# Power_Generation_-_LDO.net
KiCad netlist of a schematic drawn in Altium Designer
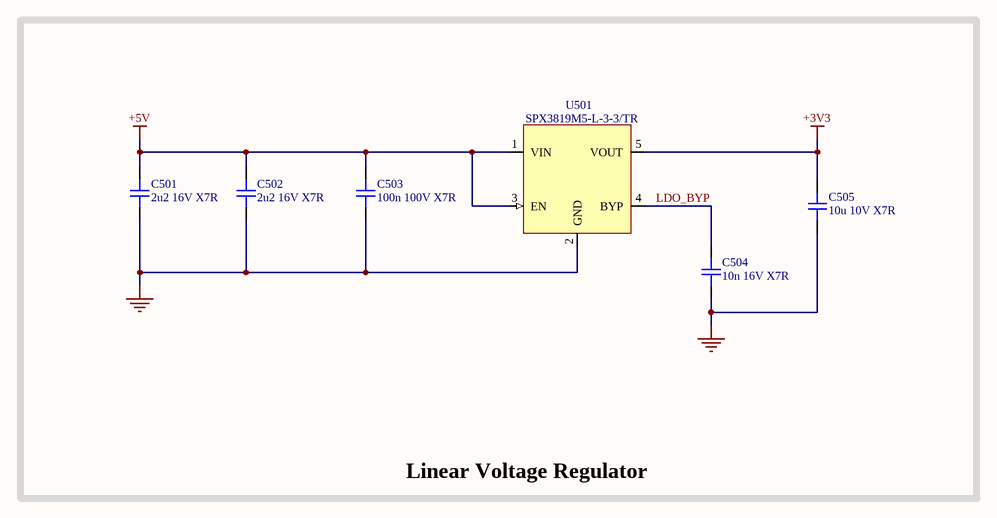
[diagram p0: Power Generation - LDO.SchDoc]

(export (version "E")
  (design (tool "Eeschema 10.0.6"))
  (components
    (comp (ref "C501")
      (value "2u2 16V X7R")
      (footprint "CAP_0805")
      (description "Capacitor SMD 0805")
      (fields
        (field (name "MANUFACTURER") "HRE")
        (field (name "MANUFACTURER PART NUMBER") "CGA0805X7R225K160MT")
      )
      (libsource (lib "Schematic-Lib-PhilsLab") (part "CAP_0805"))
    )
    (comp (ref "C502")
      (value "2u2 16V X7R")
      (footprint "CAP_0805")
      (description "Capacitor SMD 0805")
      (fields
        (field (name "MANUFACTURER") "HRE")
        (field (name "MANUFACTURER PART NUMBER") "CGA0805X7R225K160MT")
      )
      (libsource (lib "Schematic-Lib-PhilsLab") (part "CAP_0805"))
    )
    (comp (ref "C503")
      (value "100n 100V X7R")
      (footprint "CAP_0805")
      (description "Capacitor SMD 0805")
      (fields
        (field (name "MANUFACTURER") "YAGEO")
        (field (name "MANUFACTURER PART NUMBER") "CC0805JRX7R7BB104")
      )
      (libsource (lib "Schematic-Lib-PhilsLab") (part "CAP_0805"))
    )
    (comp (ref "C504")
      (value "10n 16V X7R")
      (footprint "CAP_0603")
      (description "Capacitor SMD 0603")
      (fields
        (field (name "MANUFACTURER") "YAGEO")
        (field (name "MANUFACTURER PART NUMBER") "CC0603JRX7R7BB103")
      )
      (libsource (lib "Schematic-Lib-PhilsLab") (part "CAP_0603"))
    )
    (comp (ref "C505")
      (value "10u 10V X7R")
      (footprint "CAP_0805")
      (description "Capacitor SMD 0805")
      (fields
        (field (name "MANUFACTURER") "Murata Electronics")
        (field (name "MANUFACTURER PART NUMBER") "GCM21BR71A106KE22K")
      )
      (libsource (lib "Schematic-Lib-PhilsLab") (part "CAP_0805"))
    )
    (comp (ref "U501")
      (value "SPX3819M5-L-3-3/TR")
      (footprint "SOT-23-5")
      (description "500mA +3.3V Low-Noise LDO Voltage Regulator")
      (fields (field (name "MANUFACTURER") "MaxLinear"))
      (libsource (lib "Schematic-Lib") (part "SPX3819M5-L-3-3/TR"))
    )
  )
  (nets
    (net (code "1") (name "+3V3") (class "Default")
      (node (ref "C505") (pin "1") (pinfunction "1_1") (pintype "passive"))
      (node (ref "U501") (pin "5") (pinfunction "VOUT_5") (pintype "power_in"))
    )
    (net (code "2") (name "+5V") (class "Default")
      (node (ref "C501") (pin "1") (pinfunction "1_1") (pintype "passive"))
      (node (ref "C502") (pin "1") (pinfunction "1_1") (pintype "passive"))
      (node (ref "C503") (pin "1") (pinfunction "1_1") (pintype "passive"))
      (node (ref "U501") (pin "1") (pinfunction "VIN_1") (pintype "power_in"))
      (node (ref "U501") (pin "3") (pinfunction "EN_3") (pintype "input"))
    )
    (net (code "3") (name "/LDO_BYP") (class "Default")
      (node (ref "C504") (pin "2") (pinfunction "2_2") (pintype "passive"))
      (node (ref "U501") (pin "4") (pinfunction "BYP_4") (pintype "passive"))
    )
    (net (code "4") (name "GND") (class "Default")
      (node (ref "C501") (pin "2") (pinfunction "2_2") (pintype "passive"))
      (node (ref "C502") (pin "2") (pinfunction "2_2") (pintype "passive"))
      (node (ref "C503") (pin "2") (pinfunction "2_2") (pintype "passive"))
      (node (ref "C504") (pin "1") (pinfunction "1_1") (pintype "passive"))
      (node (ref "C505") (pin "2") (pinfunction "2_2") (pintype "passive"))
      (node (ref "U501") (pin "2") (pinfunction "GND_2") (pintype "power_in"))
    )
  )
)
